# SCH_NFCPCB_2024-10-09.net
KiCad netlist of a schematic drawn in EasyEDA
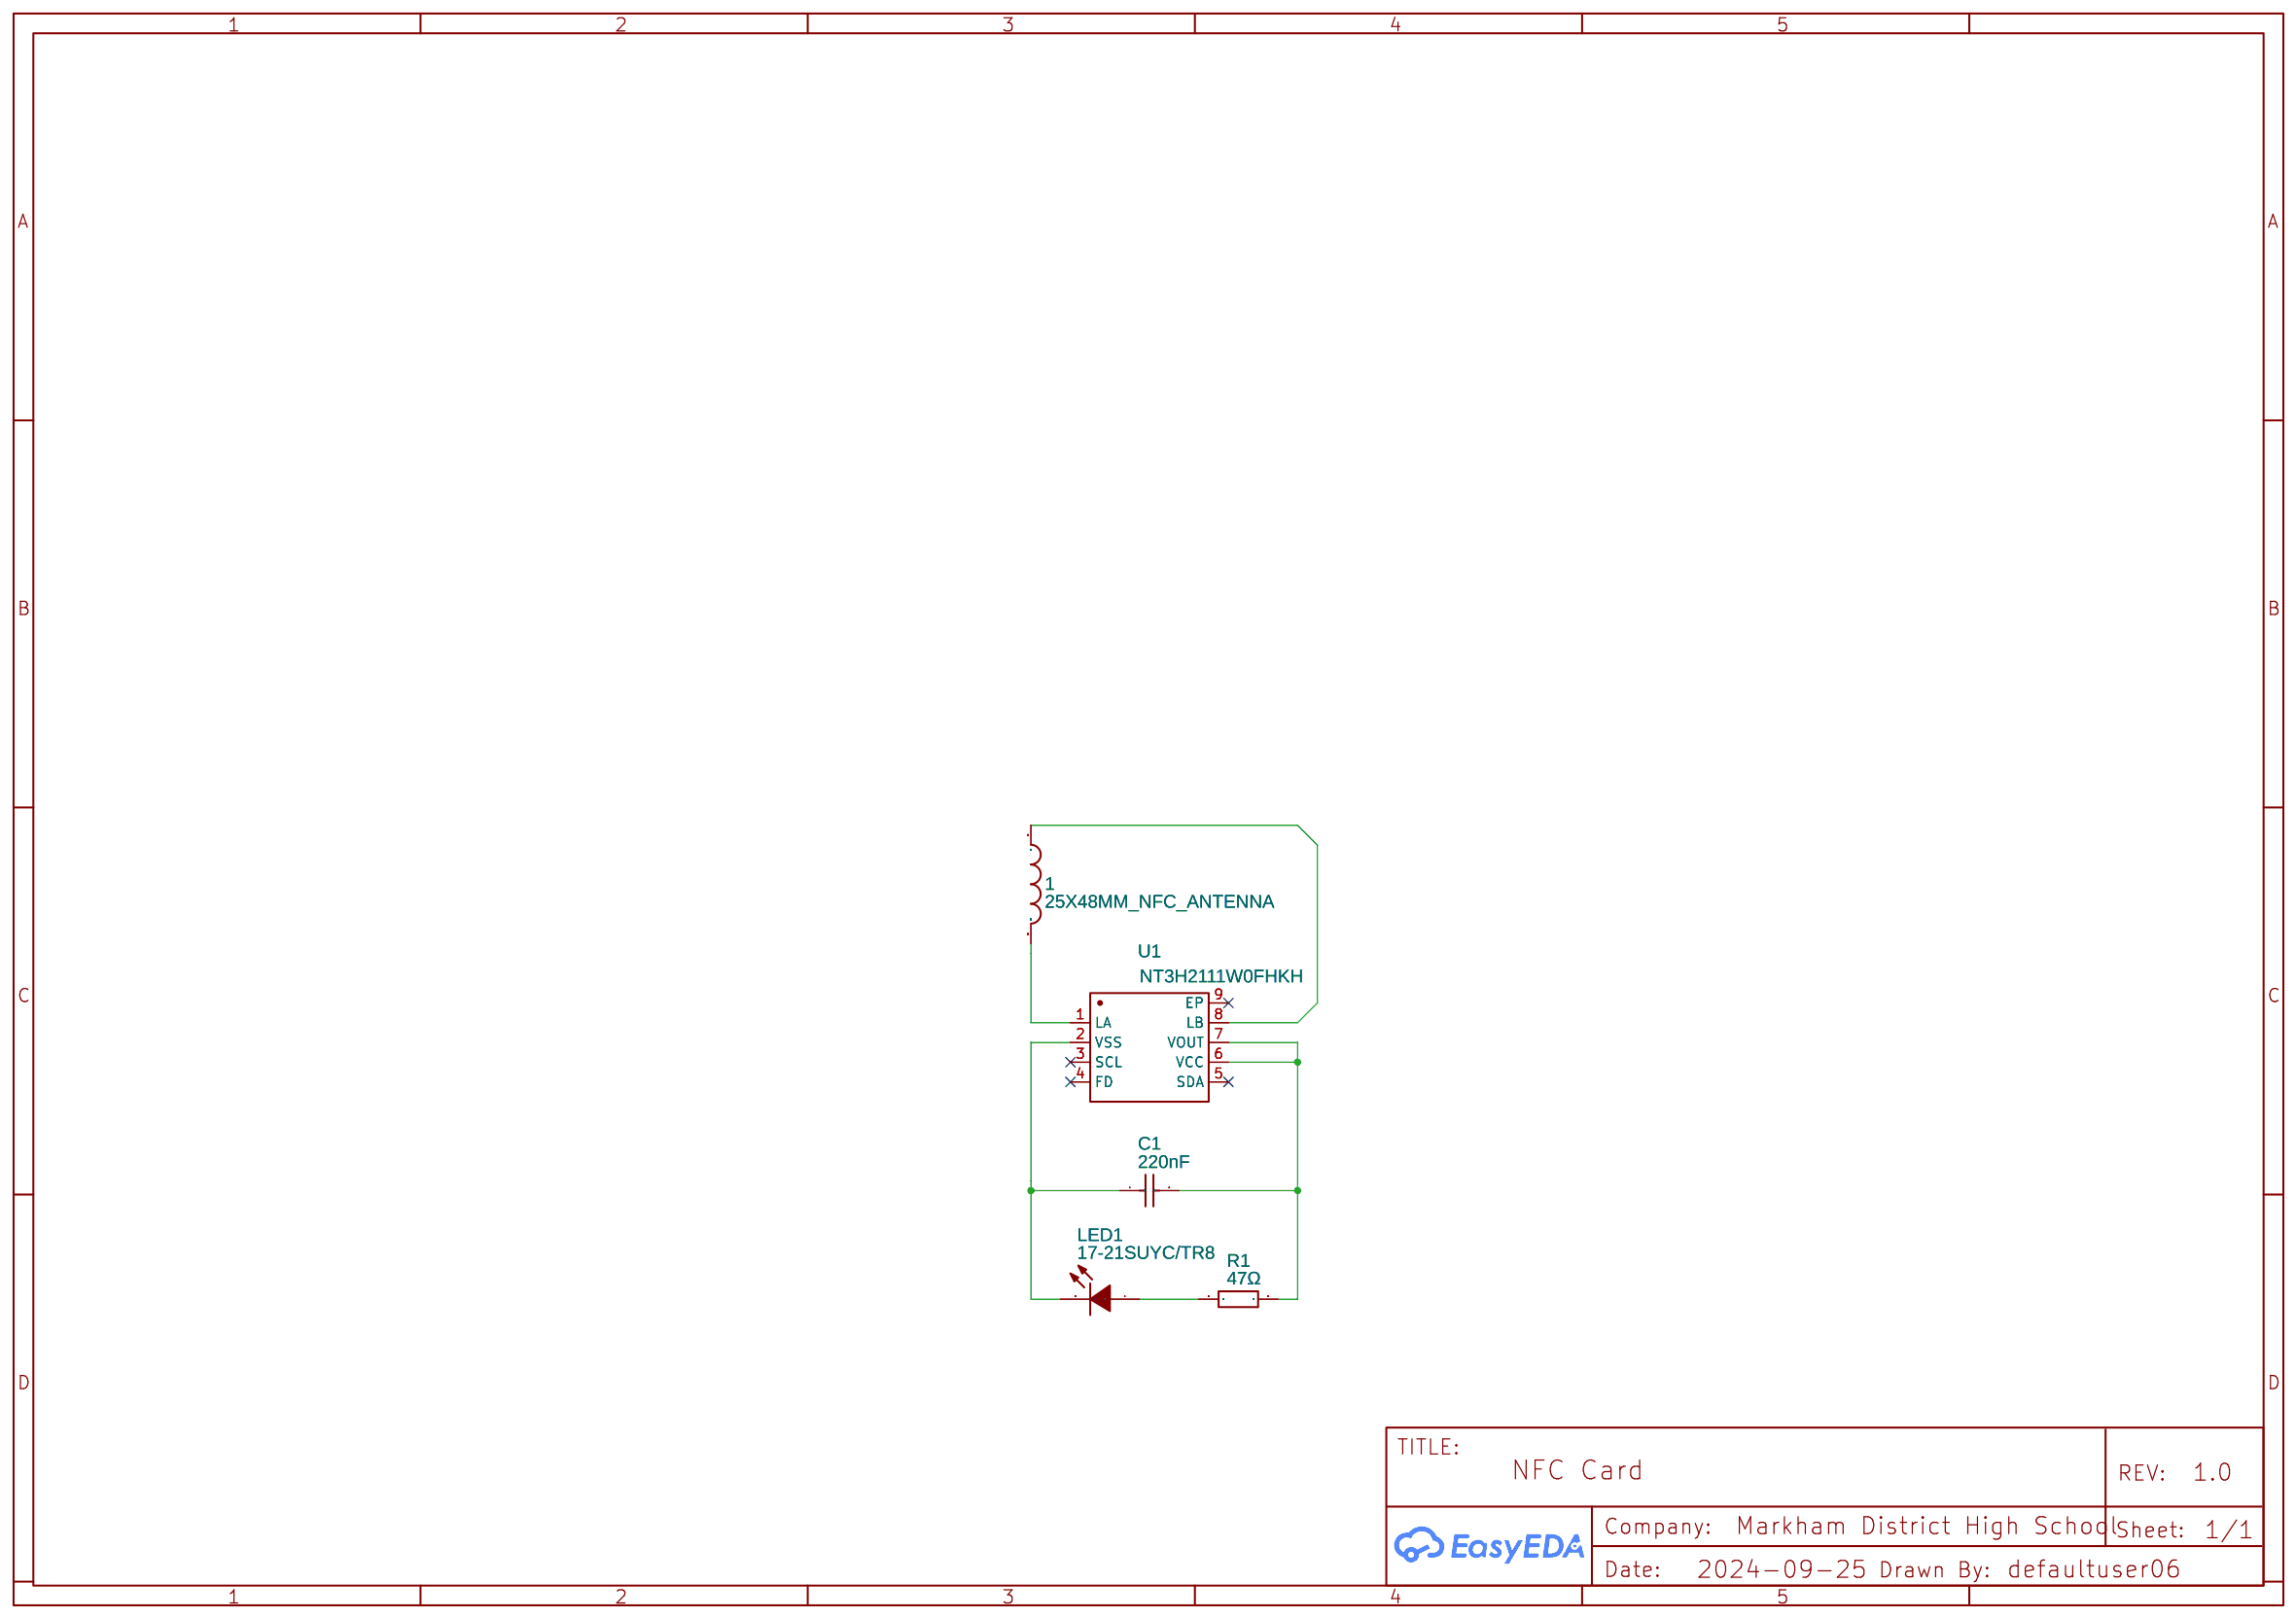
[diagram p0: schematic sheet]

(export (version "E")
  (design (tool "Eeschema 10.0.6"))
  (components
    (comp (ref "1") (value "25X48MM_NFC_ANTENNA") (libsource (lib "") (part "25X48MM_NFC_ANTENNA")))
    (comp (ref "C1")
      (value "220nF")
      (fields
        (field (name "Manufacturer Part") "CL10B224KA8NNNC")
        (field (name "Manufacturer") "SAMSUNG(三星)")
      )
      (libsource (lib "") (part "CL10B224KA8NNNC"))
    )
    (comp (ref "LED1")
      (value "17-21SUYC/TR8")
      (fields (field (name "Manufacturer Part") "KT-0805黄灯") (field (name "Manufacturer") "KENTO"))
      (libsource (lib "") (part "17-21SUYC/TR8"))
    )
    (comp (ref "R1")
      (value "47Ω")
      (fields
        (field (name "Manufacturer Part") "0603WAF470JT5E")
        (field (name "Manufacturer") "UNI-ROYAL(厚声)")
      )
      (libsource (lib "") (part "0603WAF470JT5E"))
    )
    (comp (ref "U1")
      (value "NT3H2111W0FHKH")
      (fields (field (name "Manufacturer") "NXP(恩智浦)"))
      (libsource (lib "") (part "NT3H2111W0FHKH"))
    )
  )
  (nets
    (net (code "1") (name "Net-(LED1-+)") (class "Default")
      (node (ref "LED1") (pin "1") (pinfunction "+_1") (pintype "unspecified"))
      (node (ref "R1") (pin "1") (pinfunction "1_1") (pintype "input"))
    )
    (net (code "2") (name "Net-(LED1--)") (class "Default")
      (node (ref "C1") (pin "1") (pinfunction "1_1") (pintype "input"))
      (node (ref "LED1") (pin "2") (pinfunction "-_2") (pintype "unspecified"))
      (node (ref "U1") (pin "2") (pinfunction "VSS_2") (pintype "unspecified"))
    )
    (net (code "3") (name "Net-(U1-LA)") (class "Default")
      (node (ref "1") (pin "P$2") (pinfunction "P$2_P$2") (pintype "bidirectional"))
      (node (ref "U1") (pin "1") (pinfunction "LA_1") (pintype "unspecified"))
    )
    (net (code "4") (name "Net-(U1-LB)") (class "Default")
      (node (ref "1") (pin "P$1") (pinfunction "P$1_P$1") (pintype "bidirectional"))
      (node (ref "U1") (pin "8") (pinfunction "LB_8") (pintype "unspecified"))
    )
    (net (code "5") (name "Net-(U1-VCC)") (class "Default")
      (node (ref "C1") (pin "2") (pinfunction "2_2") (pintype "input"))
      (node (ref "R1") (pin "2") (pinfunction "2_2") (pintype "input"))
      (node (ref "U1") (pin "6") (pinfunction "VCC_6") (pintype "unspecified"))
      (node (ref "U1") (pin "7") (pinfunction "VOUT_7") (pintype "unspecified"))
    )
    (net (code "6") (name "unconnected-(U1-EP-Pad9)") (class "Default")
      (node (ref "U1") (pin "9") (pinfunction "EP_9") (pintype "unspecified+no_connect"))
    )
    (net (code "7") (name "unconnected-(U1-FD-Pad4)") (class "Default")
      (node (ref "U1") (pin "4") (pinfunction "FD_4") (pintype "unspecified+no_connect"))
    )
    (net (code "8") (name "unconnected-(U1-SCL-Pad3)") (class "Default")
      (node (ref "U1") (pin "3") (pinfunction "SCL_3") (pintype "unspecified+no_connect"))
    )
    (net (code "9") (name "unconnected-(U1-SDA-Pad5)") (class "Default")
      (node (ref "U1") (pin "5") (pinfunction "SDA_5") (pintype "unspecified+no_connect"))
    )
  )
)
